# DualGreenHat_schematic.net
KiCad netlist of a schematic drawn in EasyEDA
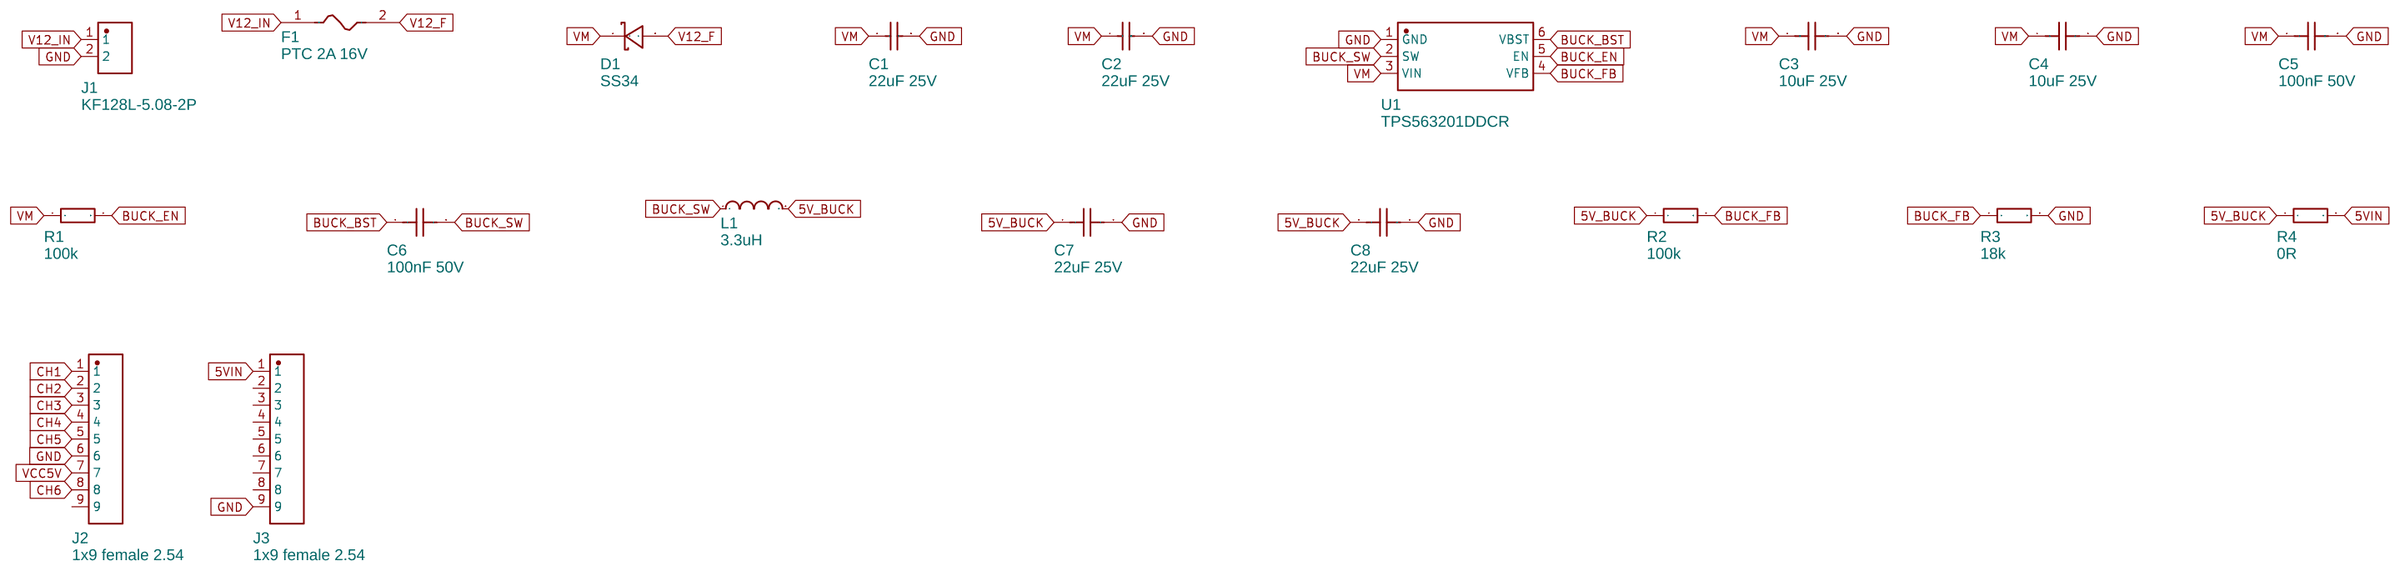
[diagram p0: Power and S3Bat]
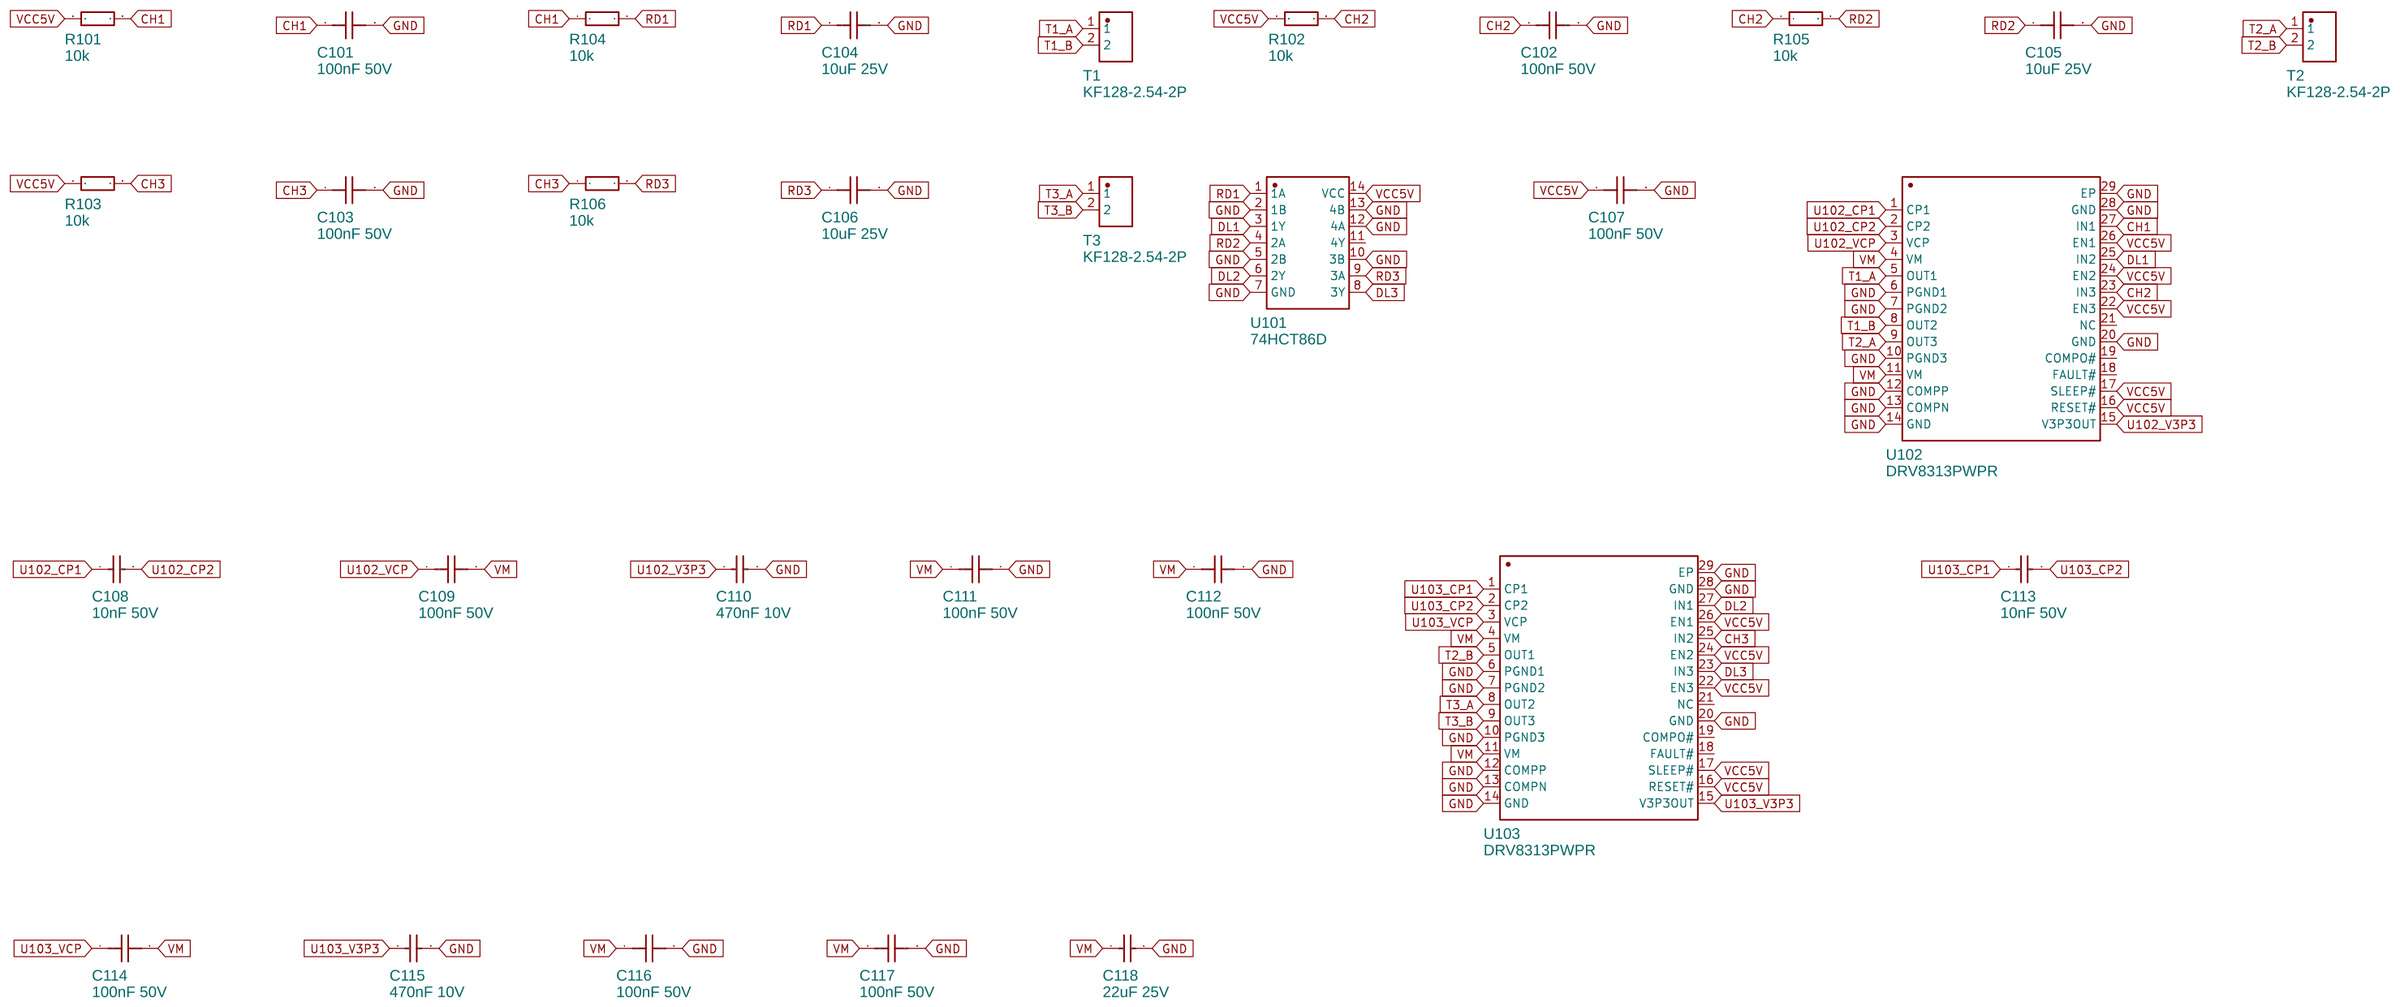
[diagram p1: Channels 1-3]
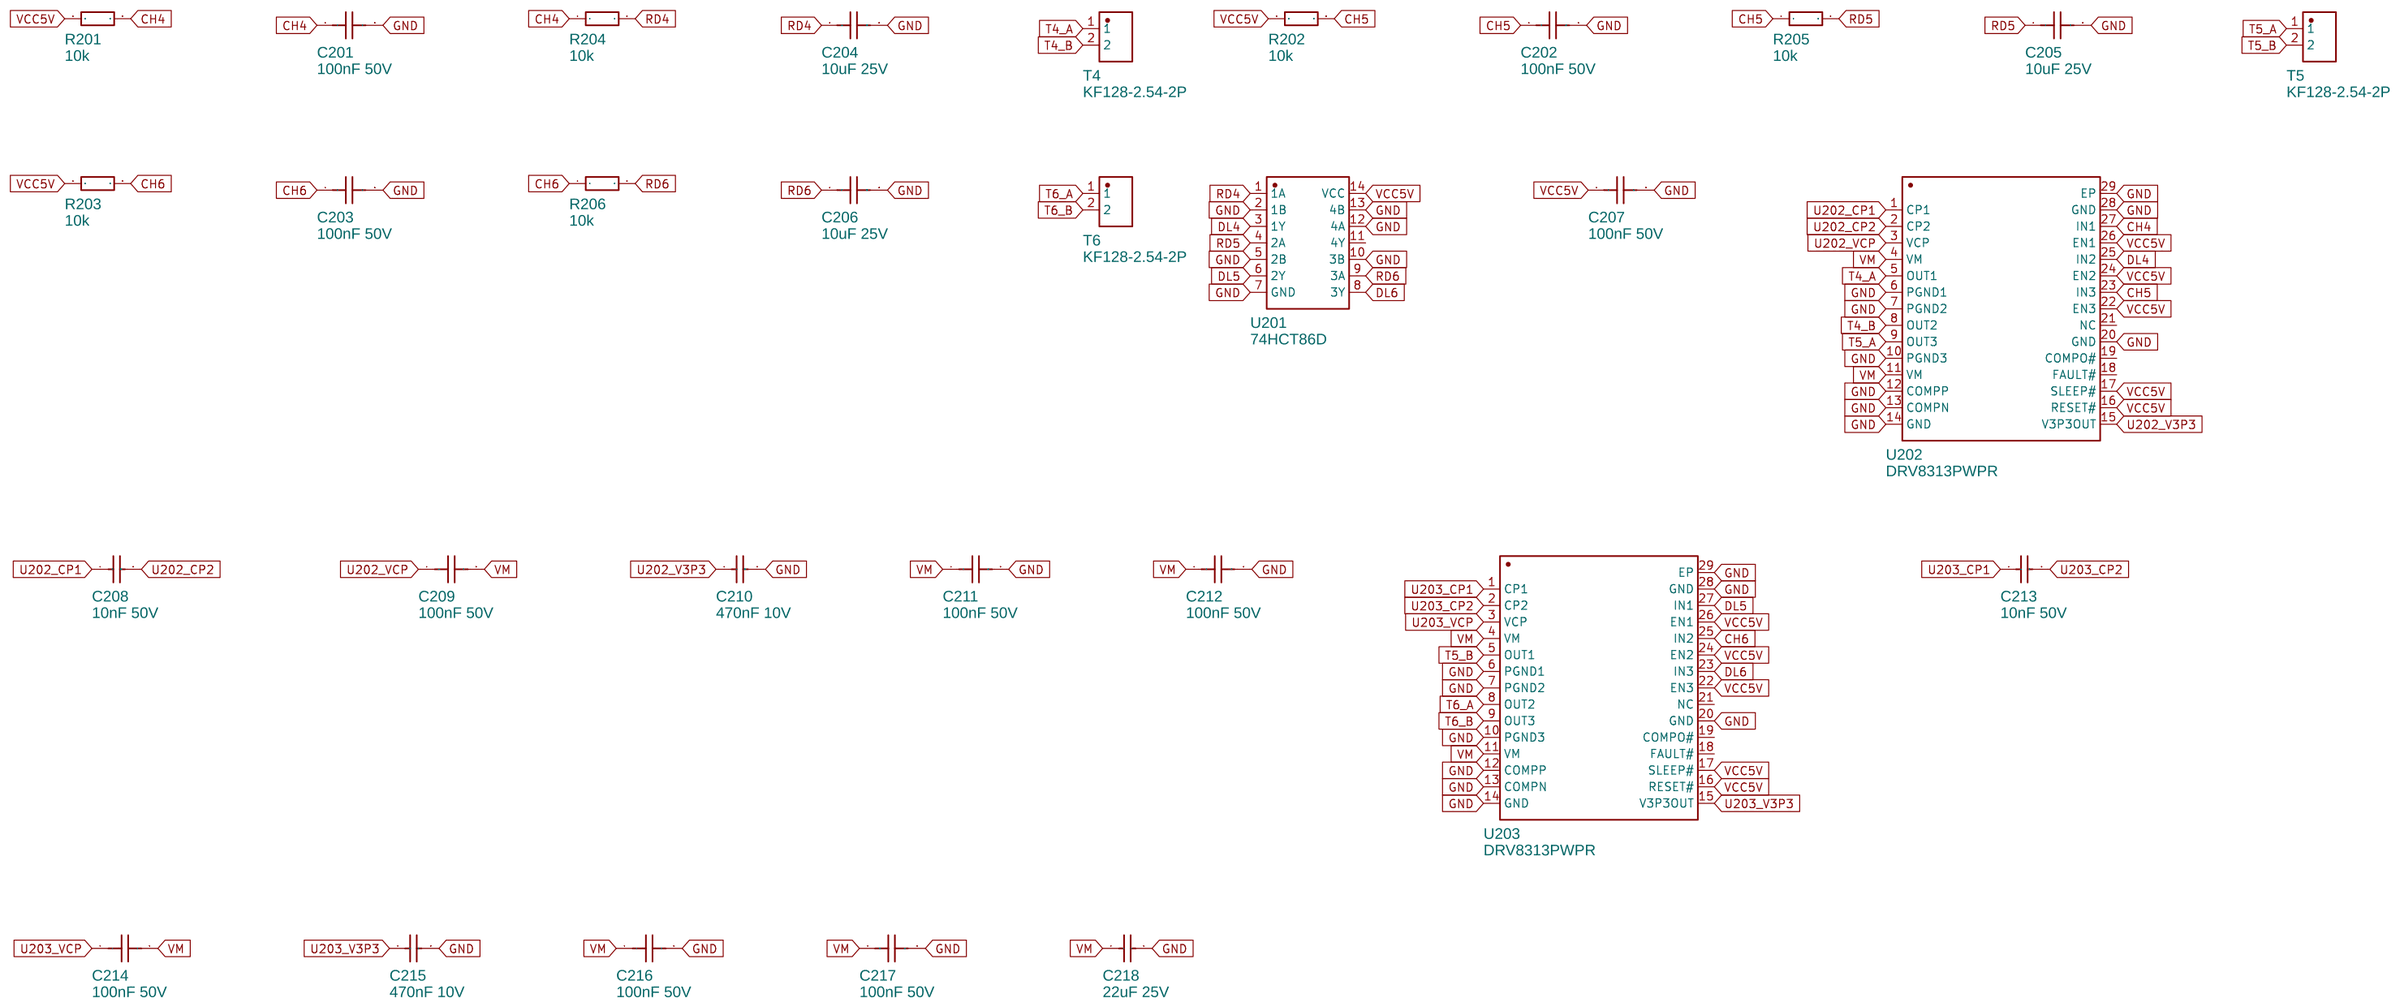
[diagram p2: Channels 4-6]

(export (version "E")
  (design (tool "Eeschema 10.0.6"))
  (components
    (comp (ref "C1")
      (value "22uF 25V")
      (fields
        (field (name "BOM_Manufacturer Part") "CL31A226KAHNNNE")
        (field (name "BOM_Supplier Part") "C12891")
      )
      (libsource (lib "") (part "CL31A226KAHNNNE_1"))
    )
    (comp (ref "C2")
      (value "22uF 25V")
      (fields
        (field (name "BOM_Manufacturer Part") "CL31A226KAHNNNE")
        (field (name "BOM_Supplier Part") "C12891")
      )
      (libsource (lib "") (part "CL31A226KAHNNNE"))
    )
    (comp (ref "C3")
      (value "10uF 25V")
      (fields
        (field (name "BOM_Manufacturer Part") "CL21A106KAYNNNE")
        (field (name "BOM_Supplier Part") "C15850")
      )
      (libsource (lib "") (part "CL21A106KAYNNNE_1"))
    )
    (comp (ref "C4")
      (value "10uF 25V")
      (fields
        (field (name "BOM_Manufacturer Part") "CL21A106KAYNNNE")
        (field (name "BOM_Supplier Part") "C15850")
      )
      (libsource (lib "") (part "CL21A106KAYNNNE"))
    )
    (comp (ref "C5")
      (value "100nF 50V")
      (fields
        (field (name "BOM_Manufacturer Part") "CL05B104KB54PNC")
        (field (name "BOM_Supplier Part") "C307331")
      )
      (libsource (lib "") (part "CL05B104KB54PNC"))
    )
    (comp (ref "C6")
      (value "100nF 50V")
      (fields
        (field (name "BOM_Manufacturer Part") "CL05B104KB54PNC")
        (field (name "BOM_Supplier Part") "C307331")
      )
      (libsource (lib "") (part "CL05B104KB54PNC"))
    )
    (comp (ref "C7")
      (value "22uF 25V")
      (fields
        (field (name "BOM_Manufacturer Part") "CL21A226MAQNNNE")
        (field (name "BOM_Supplier Part") "C45783")
      )
      (libsource (lib "") (part "CL21A226MAQNNNE"))
    )
    (comp (ref "C8")
      (value "22uF 25V")
      (fields
        (field (name "BOM_Manufacturer Part") "CL21A226MAQNNNE")
        (field (name "BOM_Supplier Part") "C45783")
      )
      (libsource (lib "") (part "CL21A226MAQNNNE"))
    )
    (comp (ref "D1")
      (value "SS34")
      (fields (field (name "BOM_Supplier Part") "C8678"))
      (libsource (lib "") (part "SS34"))
    )
    (comp (ref "F1")
      (value "PTC 2A 16V")
      (fields
        (field (name "BOM_Manufacturer Part") "SMD1812P200TF16")
        (field (name "BOM_Supplier Part") "C20812")
      )
      (libsource (lib "") (part "SMD1812P200TF16"))
    )
    (comp (ref "J1")
      (value "KF128L-5.08-2P")
      (fields (field (name "BOM_Supplier Part") "C474940"))
      (libsource (lib "") (part "KF128L-5.08-2P"))
    )
    (comp (ref "J2")
      (value "1x9 female 2.54")
      (fields
        (field (name "BOM_Manufacturer Part") "HX PM2.54-1x9P ZC-Y")
        (field (name "BOM_Supplier Part") "C22438159")
      )
      (libsource (lib "") (part "HX PM2.54-1x9P ZC-Y"))
    )
    (comp (ref "J3")
      (value "1x9 female 2.54")
      (fields
        (field (name "BOM_Manufacturer Part") "HX PM2.54-1x9P ZC-Y")
        (field (name "BOM_Supplier Part") "C22438159")
      )
      (libsource (lib "") (part "HX PM2.54-1x9P ZC-Y"))
    )
    (comp (ref "L1")
      (value "3.3uH")
      (fields
        (field (name "BOM_Manufacturer Part") "SWPA4030S3R3MT")
        (field (name "BOM_Supplier Part") "C15269")
      )
      (libsource (lib "") (part "SWPA4030S3R3MT"))
    )
    (comp (ref "R1")
      (value "100k")
      (fields
        (field (name "BOM_Manufacturer Part") "0402WGF1003TCE")
        (field (name "BOM_Supplier Part") "C25741")
      )
      (libsource (lib "") (part "0402WGF1003TCE"))
    )
    (comp (ref "R2")
      (value "100k")
      (fields
        (field (name "BOM_Manufacturer Part") "0402WGF1003TCE")
        (field (name "BOM_Supplier Part") "C25741")
      )
      (libsource (lib "") (part "0402WGF1003TCE"))
    )
    (comp (ref "R3")
      (value "18k")
      (fields
        (field (name "BOM_Manufacturer Part") "0603WAF1802T5E")
        (field (name "BOM_Supplier Part") "C25810")
      )
      (libsource (lib "") (part "0603WAF1802T5E"))
    )
    (comp (ref "R4")
      (value "0R")
      (fields
        (field (name "BOM_Manufacturer Part") "0805W8F0000T5E")
        (field (name "BOM_Supplier Part") "C17477")
      )
      (libsource (lib "") (part "0805W8F0000T5E"))
    )
    (comp (ref "U1")
      (value "TPS563201DDCR")
      (fields (field (name "BOM_Supplier Part") "C116592"))
      (libsource (lib "") (part "TPS563201DDCR"))
    )
    (comp (ref "C101")
      (value "100nF 50V")
      (fields
        (field (name "BOM_Manufacturer Part") "CL05B104KB54PNC")
        (field (name "BOM_Supplier Part") "C307331")
      )
      (libsource (lib "") (part "CL05B104KB54PNC_1"))
    )
    (comp (ref "C102")
      (value "100nF 50V")
      (fields
        (field (name "BOM_Manufacturer Part") "CL05B104KB54PNC")
        (field (name "BOM_Supplier Part") "C307331")
      )
      (libsource (lib "") (part "CL05B104KB54PNC_1"))
    )
    (comp (ref "C103")
      (value "100nF 50V")
      (fields
        (field (name "BOM_Manufacturer Part") "CL05B104KB54PNC")
        (field (name "BOM_Supplier Part") "C307331")
      )
      (libsource (lib "") (part "CL05B104KB54PNC_1"))
    )
    (comp (ref "C104")
      (value "10uF 25V")
      (fields
        (field (name "BOM_Manufacturer Part") "CL21A106KAYNNNE")
        (field (name "BOM_Supplier Part") "C15850")
      )
      (libsource (lib "") (part "CL21A106KAYNNNE"))
    )
    (comp (ref "C105")
      (value "10uF 25V")
      (fields
        (field (name "BOM_Manufacturer Part") "CL21A106KAYNNNE")
        (field (name "BOM_Supplier Part") "C15850")
      )
      (libsource (lib "") (part "CL21A106KAYNNNE"))
    )
    (comp (ref "C106")
      (value "10uF 25V")
      (fields
        (field (name "BOM_Manufacturer Part") "CL21A106KAYNNNE")
        (field (name "BOM_Supplier Part") "C15850")
      )
      (libsource (lib "") (part "CL21A106KAYNNNE"))
    )
    (comp (ref "C107")
      (value "100nF 50V")
      (fields
        (field (name "BOM_Manufacturer Part") "CL05B104KB54PNC")
        (field (name "BOM_Supplier Part") "C307331")
      )
      (libsource (lib "") (part "CL05B104KB54PNC_1"))
    )
    (comp (ref "C108")
      (value "10nF 50V")
      (fields
        (field (name "BOM_Manufacturer Part") "CL05B103KB5NNNC")
        (field (name "BOM_Supplier Part") "C15195")
      )
      (libsource (lib "") (part "CL05B103KB5NNNC"))
    )
    (comp (ref "C109")
      (value "100nF 50V")
      (fields
        (field (name "BOM_Manufacturer Part") "CL05B104KB54PNC")
        (field (name "BOM_Supplier Part") "C307331")
      )
      (libsource (lib "") (part "CL05B104KB54PNC"))
    )
    (comp (ref "C110")
      (value "470nF 10V")
      (fields
        (field (name "BOM_Manufacturer Part") "CL05A474KP5NNNC")
        (field (name "BOM_Supplier Part") "C47339")
      )
      (libsource (lib "") (part "CL05A474KP5NNNC"))
    )
    (comp (ref "C111")
      (value "100nF 50V")
      (fields
        (field (name "BOM_Manufacturer Part") "CL05B104KB54PNC")
        (field (name "BOM_Supplier Part") "C307331")
      )
      (libsource (lib "") (part "CL05B104KB54PNC"))
    )
    (comp (ref "C112")
      (value "100nF 50V")
      (fields
        (field (name "BOM_Manufacturer Part") "CL05B104KB54PNC")
        (field (name "BOM_Supplier Part") "C307331")
      )
      (libsource (lib "") (part "CL05B104KB54PNC_1"))
    )
    (comp (ref "C113")
      (value "10nF 50V")
      (fields
        (field (name "BOM_Manufacturer Part") "CL05B103KB5NNNC")
        (field (name "BOM_Supplier Part") "C15195")
      )
      (libsource (lib "") (part "CL05B103KB5NNNC_1"))
    )
    (comp (ref "C114")
      (value "100nF 50V")
      (fields
        (field (name "BOM_Manufacturer Part") "CL05B104KB54PNC")
        (field (name "BOM_Supplier Part") "C307331")
      )
      (libsource (lib "") (part "CL05B104KB54PNC"))
    )
    (comp (ref "C115")
      (value "470nF 10V")
      (fields
        (field (name "BOM_Manufacturer Part") "CL05A474KP5NNNC")
        (field (name "BOM_Supplier Part") "C47339")
      )
      (libsource (lib "") (part "CL05A474KP5NNNC"))
    )
    (comp (ref "C116")
      (value "100nF 50V")
      (fields
        (field (name "BOM_Manufacturer Part") "CL05B104KB54PNC")
        (field (name "BOM_Supplier Part") "C307331")
      )
      (libsource (lib "") (part "CL05B104KB54PNC"))
    )
    (comp (ref "C117")
      (value "100nF 50V")
      (fields
        (field (name "BOM_Manufacturer Part") "CL05B104KB54PNC")
        (field (name "BOM_Supplier Part") "C307331")
      )
      (libsource (lib "") (part "CL05B104KB54PNC_1"))
    )
    (comp (ref "C118")
      (value "22uF 25V")
      (fields
        (field (name "BOM_Manufacturer Part") "CL31A226KAHNNNE")
        (field (name "BOM_Supplier Part") "C12891")
      )
      (libsource (lib "") (part "CL31A226KAHNNNE"))
    )
    (comp (ref "R101")
      (value "10k")
      (fields
        (field (name "BOM_Manufacturer Part") "0402WGF1002TCE")
        (field (name "BOM_Supplier Part") "C25744")
      )
      (libsource (lib "") (part "0402WGF1002TCE"))
    )
    (comp (ref "R102")
      (value "10k")
      (fields
        (field (name "BOM_Manufacturer Part") "0402WGF1002TCE")
        (field (name "BOM_Supplier Part") "C25744")
      )
      (libsource (lib "") (part "0402WGF1002TCE"))
    )
    (comp (ref "R103")
      (value "10k")
      (fields
        (field (name "BOM_Manufacturer Part") "0402WGF1002TCE")
        (field (name "BOM_Supplier Part") "C25744")
      )
      (libsource (lib "") (part "0402WGF1002TCE"))
    )
    (comp (ref "R104")
      (value "10k")
      (fields
        (field (name "BOM_Manufacturer Part") "0402WGF1002TCE")
        (field (name "BOM_Supplier Part") "C25744")
      )
      (libsource (lib "") (part "0402WGF1002TCE"))
    )
    (comp (ref "R105")
      (value "10k")
      (fields
        (field (name "BOM_Manufacturer Part") "0402WGF1002TCE")
        (field (name "BOM_Supplier Part") "C25744")
      )
      (libsource (lib "") (part "0402WGF1002TCE"))
    )
    (comp (ref "R106")
      (value "10k")
      (fields
        (field (name "BOM_Manufacturer Part") "0402WGF1002TCE")
        (field (name "BOM_Supplier Part") "C25744")
      )
      (libsource (lib "") (part "0402WGF1002TCE"))
    )
    (comp (ref "T1")
      (value "KF128-2.54-2P")
      (fields (field (name "BOM_Supplier Part") "C474920"))
      (libsource (lib "") (part "KF128-2.54-2P"))
    )
    (comp (ref "T2")
      (value "KF128-2.54-2P")
      (fields (field (name "BOM_Supplier Part") "C474920"))
      (libsource (lib "") (part "KF128-2.54-2P"))
    )
    (comp (ref "T3")
      (value "KF128-2.54-2P")
      (fields (field (name "BOM_Supplier Part") "C474920"))
      (libsource (lib "") (part "KF128-2.54-2P"))
    )
    (comp (ref "U101")
      (value "74HCT86D")
      (fields
        (field (name "BOM_Manufacturer Part") "74HCT86D,653")
        (field (name "BOM_Supplier Part") "C6005")
      )
      (libsource (lib "") (part "74HCT86D,653"))
    )
    (comp (ref "U102")
      (value "DRV8313PWPR")
      (fields (field (name "BOM_Supplier Part") "C92482"))
      (libsource (lib "") (part "DRV8313PWPR"))
    )
    (comp (ref "U103")
      (value "DRV8313PWPR")
      (fields (field (name "BOM_Supplier Part") "C92482"))
      (libsource (lib "") (part "DRV8313PWPR"))
    )
    (comp (ref "C201")
      (value "100nF 50V")
      (fields
        (field (name "BOM_Manufacturer Part") "CL05B104KB54PNC")
        (field (name "BOM_Supplier Part") "C307331")
      )
      (libsource (lib "") (part "CL05B104KB54PNC"))
    )
    (comp (ref "C202")
      (value "100nF 50V")
      (fields
        (field (name "BOM_Manufacturer Part") "CL05B104KB54PNC")
        (field (name "BOM_Supplier Part") "C307331")
      )
      (libsource (lib "") (part "CL05B104KB54PNC"))
    )
    (comp (ref "C203")
      (value "100nF 50V")
      (fields
        (field (name "BOM_Manufacturer Part") "CL05B104KB54PNC")
        (field (name "BOM_Supplier Part") "C307331")
      )
      (libsource (lib "") (part "CL05B104KB54PNC"))
    )
    (comp (ref "C204")
      (value "10uF 25V")
      (fields
        (field (name "BOM_Manufacturer Part") "CL21A106KAYNNNE")
        (field (name "BOM_Supplier Part") "C15850")
      )
      (libsource (lib "") (part "CL21A106KAYNNNE"))
    )
    (comp (ref "C205")
      (value "10uF 25V")
      (fields
        (field (name "BOM_Manufacturer Part") "CL21A106KAYNNNE")
        (field (name "BOM_Supplier Part") "C15850")
      )
      (libsource (lib "") (part "CL21A106KAYNNNE"))
    )
    (comp (ref "C206")
      (value "10uF 25V")
      (fields
        (field (name "BOM_Manufacturer Part") "CL21A106KAYNNNE")
        (field (name "BOM_Supplier Part") "C15850")
      )
      (libsource (lib "") (part "CL21A106KAYNNNE"))
    )
    (comp (ref "C207")
      (value "100nF 50V")
      (fields
        (field (name "BOM_Manufacturer Part") "CL05B104KB54PNC")
        (field (name "BOM_Supplier Part") "C307331")
      )
      (libsource (lib "") (part "CL05B104KB54PNC"))
    )
    (comp (ref "C208")
      (value "10nF 50V")
      (fields
        (field (name "BOM_Manufacturer Part") "CL05B103KB5NNNC")
        (field (name "BOM_Supplier Part") "C15195")
      )
      (libsource (lib "") (part "CL05B103KB5NNNC_1"))
    )
    (comp (ref "C209")
      (value "100nF 50V")
      (fields
        (field (name "BOM_Manufacturer Part") "CL05B104KB54PNC")
        (field (name "BOM_Supplier Part") "C307331")
      )
      (libsource (lib "") (part "CL05B104KB54PNC_1"))
    )
    (comp (ref "C210")
      (value "470nF 10V")
      (fields
        (field (name "BOM_Manufacturer Part") "CL05A474KP5NNNC")
        (field (name "BOM_Supplier Part") "C47339")
      )
      (libsource (lib "") (part "CL05A474KP5NNNC"))
    )
    (comp (ref "C211")
      (value "100nF 50V")
      (fields
        (field (name "BOM_Manufacturer Part") "CL05B104KB54PNC")
        (field (name "BOM_Supplier Part") "C307331")
      )
      (libsource (lib "") (part "CL05B104KB54PNC_1"))
    )
    (comp (ref "C212")
      (value "100nF 50V")
      (fields
        (field (name "BOM_Manufacturer Part") "CL05B104KB54PNC")
        (field (name "BOM_Supplier Part") "C307331")
      )
      (libsource (lib "") (part "CL05B104KB54PNC"))
    )
    (comp (ref "C213")
      (value "10nF 50V")
      (fields
        (field (name "BOM_Manufacturer Part") "CL05B103KB5NNNC")
        (field (name "BOM_Supplier Part") "C15195")
      )
      (libsource (lib "") (part "CL05B103KB5NNNC"))
    )
    (comp (ref "C214")
      (value "100nF 50V")
      (fields
        (field (name "BOM_Manufacturer Part") "CL05B104KB54PNC")
        (field (name "BOM_Supplier Part") "C307331")
      )
      (libsource (lib "") (part "CL05B104KB54PNC_1"))
    )
    (comp (ref "C215")
      (value "470nF 10V")
      (fields
        (field (name "BOM_Manufacturer Part") "CL05A474KP5NNNC")
        (field (name "BOM_Supplier Part") "C47339")
      )
      (libsource (lib "") (part "CL05A474KP5NNNC"))
    )
    (comp (ref "C216")
      (value "100nF 50V")
      (fields
        (field (name "BOM_Manufacturer Part") "CL05B104KB54PNC")
        (field (name "BOM_Supplier Part") "C307331")
      )
      (libsource (lib "") (part "CL05B104KB54PNC_1"))
    )
    (comp (ref "C217")
      (value "100nF 50V")
      (fields
        (field (name "BOM_Manufacturer Part") "CL05B104KB54PNC")
        (field (name "BOM_Supplier Part") "C307331")
      )
      (libsource (lib "") (part "CL05B104KB54PNC"))
    )
    (comp (ref "C218")
      (value "22uF 25V")
      (fields
        (field (name "BOM_Manufacturer Part") "CL31A226KAHNNNE")
        (field (name "BOM_Supplier Part") "C12891")
      )
      (libsource (lib "") (part "CL31A226KAHNNNE"))
    )
    (comp (ref "R201")
      (value "10k")
      (fields
        (field (name "BOM_Manufacturer Part") "0402WGF1002TCE")
        (field (name "BOM_Supplier Part") "C25744")
      )
      (libsource (lib "") (part "0402WGF1002TCE"))
    )
    (comp (ref "R202")
      (value "10k")
      (fields
        (field (name "BOM_Manufacturer Part") "0402WGF1002TCE")
        (field (name "BOM_Supplier Part") "C25744")
      )
      (libsource (lib "") (part "0402WGF1002TCE"))
    )
    (comp (ref "R203")
      (value "10k")
      (fields
        (field (name "BOM_Manufacturer Part") "0402WGF1002TCE")
        (field (name "BOM_Supplier Part") "C25744")
      )
      (libsource (lib "") (part "0402WGF1002TCE"))
    )
    (comp (ref "R204")
      (value "10k")
      (fields
        (field (name "BOM_Manufacturer Part") "0402WGF1002TCE")
        (field (name "BOM_Supplier Part") "C25744")
      )
      (libsource (lib "") (part "0402WGF1002TCE"))
    )
    (comp (ref "R205")
      (value "10k")
      (fields
        (field (name "BOM_Manufacturer Part") "0402WGF1002TCE")
        (field (name "BOM_Supplier Part") "C25744")
      )
      (libsource (lib "") (part "0402WGF1002TCE"))
    )
    (comp (ref "R206")
      (value "10k")
      (fields
        (field (name "BOM_Manufacturer Part") "0402WGF1002TCE")
        (field (name "BOM_Supplier Part") "C25744")
      )
      (libsource (lib "") (part "0402WGF1002TCE"))
    )
    (comp (ref "T4")
      (value "KF128-2.54-2P")
      (fields (field (name "BOM_Supplier Part") "C474920"))
      (libsource (lib "") (part "KF128-2.54-2P"))
    )
    (comp (ref "T5")
      (value "KF128-2.54-2P")
      (fields (field (name "BOM_Supplier Part") "C474920"))
      (libsource (lib "") (part "KF128-2.54-2P"))
    )
    (comp (ref "T6")
      (value "KF128-2.54-2P")
      (fields (field (name "BOM_Supplier Part") "C474920"))
      (libsource (lib "") (part "KF128-2.54-2P"))
    )
    (comp (ref "U201")
      (value "74HCT86D")
      (fields
        (field (name "BOM_Manufacturer Part") "74HCT86D,653")
        (field (name "BOM_Supplier Part") "C6005")
      )
      (libsource (lib "") (part "74HCT86D,653"))
    )
    (comp (ref "U202")
      (value "DRV8313PWPR")
      (fields (field (name "BOM_Supplier Part") "C92482"))
      (libsource (lib "") (part "DRV8313PWPR"))
    )
    (comp (ref "U203")
      (value "DRV8313PWPR")
      (fields (field (name "BOM_Supplier Part") "C92482"))
      (libsource (lib "") (part "DRV8313PWPR"))
    )
  )
  (nets
    (net (code "1") (name "5VIN") (class "Default")
      (node (ref "J3") (pin "1") (pinfunction "1_1") (pintype "unspecified"))
      (node (ref "R4") (pin "2") (pinfunction "2_2") (pintype "input"))
    )
    (net (code "2") (name "5V_BUCK") (class "Default")
      (node (ref "C7") (pin "1") (pinfunction "1_1") (pintype "unspecified"))
      (node (ref "C8") (pin "1") (pinfunction "1_1") (pintype "unspecified"))
      (node (ref "L1") (pin "2") (pinfunction "2_2") (pintype "unspecified"))
      (node (ref "R2") (pin "1") (pinfunction "1_1") (pintype "input"))
      (node (ref "R4") (pin "1") (pinfunction "1_1") (pintype "input"))
    )
    (net (code "3") (name "BUCK_BST") (class "Default")
      (node (ref "C6") (pin "1") (pinfunction "1_1") (pintype "unspecified"))
      (node (ref "U1") (pin "6") (pinfunction "VBST_6") (pintype "unspecified"))
    )
    (net (code "4") (name "BUCK_EN") (class "Default")
      (node (ref "R1") (pin "2") (pinfunction "2_2") (pintype "input"))
      (node (ref "U1") (pin "5") (pinfunction "EN_5") (pintype "unspecified"))
    )
    (net (code "5") (name "BUCK_FB") (class "Default")
      (node (ref "R2") (pin "2") (pinfunction "2_2") (pintype "input"))
      (node (ref "R3") (pin "1") (pinfunction "1_1") (pintype "input"))
      (node (ref "U1") (pin "4") (pinfunction "VFB_4") (pintype "unspecified"))
    )
    (net (code "6") (name "BUCK_SW") (class "Default")
      (node (ref "C6") (pin "2") (pinfunction "2_2") (pintype "unspecified"))
      (node (ref "L1") (pin "1") (pinfunction "1_1") (pintype "unspecified"))
      (node (ref "U1") (pin "2") (pinfunction "SW_2") (pintype "unspecified"))
    )
    (net (code "7") (name "CH1") (class "Default")
      (node (ref "C101") (pin "1") (pinfunction "1_1") (pintype "unspecified"))
      (node (ref "J2") (pin "1") (pinfunction "1_1") (pintype "unspecified"))
      (node (ref "R101") (pin "2") (pinfunction "2_2") (pintype "input"))
      (node (ref "R104") (pin "1") (pinfunction "1_1") (pintype "input"))
      (node (ref "U102") (pin "27") (pinfunction "IN1_27") (pintype "unspecified"))
    )
    (net (code "8") (name "CH2") (class "Default")
      (node (ref "C102") (pin "1") (pinfunction "1_1") (pintype "unspecified"))
      (node (ref "J2") (pin "2") (pinfunction "2_2") (pintype "unspecified"))
      (node (ref "R102") (pin "2") (pinfunction "2_2") (pintype "input"))
      (node (ref "R105") (pin "1") (pinfunction "1_1") (pintype "input"))
      (node (ref "U102") (pin "23") (pinfunction "IN3_23") (pintype "unspecified"))
    )
    (net (code "9") (name "CH3") (class "Default")
      (node (ref "C103") (pin "1") (pinfunction "1_1") (pintype "unspecified"))
      (node (ref "J2") (pin "3") (pinfunction "3_3") (pintype "unspecified"))
      (node (ref "R103") (pin "2") (pinfunction "2_2") (pintype "input"))
      (node (ref "R106") (pin "1") (pinfunction "1_1") (pintype "input"))
      (node (ref "U103") (pin "25") (pinfunction "IN2_25") (pintype "unspecified"))
    )
    (net (code "10") (name "CH4") (class "Default")
      (node (ref "C201") (pin "1") (pinfunction "1_1") (pintype "unspecified"))
      (node (ref "J2") (pin "4") (pinfunction "4_4") (pintype "unspecified"))
      (node (ref "R201") (pin "2") (pinfunction "2_2") (pintype "input"))
      (node (ref "R204") (pin "1") (pinfunction "1_1") (pintype "input"))
      (node (ref "U202") (pin "27") (pinfunction "IN1_27") (pintype "unspecified"))
    )
    (net (code "11") (name "CH5") (class "Default")
      (node (ref "C202") (pin "1") (pinfunction "1_1") (pintype "unspecified"))
      (node (ref "J2") (pin "5") (pinfunction "5_5") (pintype "unspecified"))
      (node (ref "R202") (pin "2") (pinfunction "2_2") (pintype "input"))
      (node (ref "R205") (pin "1") (pinfunction "1_1") (pintype "input"))
      (node (ref "U202") (pin "23") (pinfunction "IN3_23") (pintype "unspecified"))
    )
    (net (code "12") (name "CH6") (class "Default")
      (node (ref "C203") (pin "1") (pinfunction "1_1") (pintype "unspecified"))
      (node (ref "J2") (pin "8") (pinfunction "8_8") (pintype "unspecified"))
      (node (ref "R203") (pin "2") (pinfunction "2_2") (pintype "input"))
      (node (ref "R206") (pin "1") (pinfunction "1_1") (pintype "input"))
      (node (ref "U203") (pin "25") (pinfunction "IN2_25") (pintype "unspecified"))
    )
    (net (code "13") (name "DL1") (class "Default")
      (node (ref "U101") (pin "3") (pinfunction "1Y_3") (pintype "unspecified"))
      (node (ref "U102") (pin "25") (pinfunction "IN2_25") (pintype "unspecified"))
    )
    (net (code "14") (name "DL2") (class "Default")
      (node (ref "U101") (pin "6") (pinfunction "2Y_6") (pintype "unspecified"))
      (node (ref "U103") (pin "27") (pinfunction "IN1_27") (pintype "unspecified"))
    )
    (net (code "15") (name "DL3") (class "Default")
      (node (ref "U101") (pin "8") (pinfunction "3Y_8") (pintype "unspecified"))
      (node (ref "U103") (pin "23") (pinfunction "IN3_23") (pintype "unspecified"))
    )
    (net (code "16") (name "DL4") (class "Default")
      (node (ref "U201") (pin "3") (pinfunction "1Y_3") (pintype "unspecified"))
      (node (ref "U202") (pin "25") (pinfunction "IN2_25") (pintype "unspecified"))
    )
    (net (code "17") (name "DL5") (class "Default")
      (node (ref "U201") (pin "6") (pinfunction "2Y_6") (pintype "unspecified"))
      (node (ref "U203") (pin "27") (pinfunction "IN1_27") (pintype "unspecified"))
    )
    (net (code "18") (name "DL6") (class "Default")
      (node (ref "U201") (pin "8") (pinfunction "3Y_8") (pintype "unspecified"))
      (node (ref "U203") (pin "23") (pinfunction "IN3_23") (pintype "unspecified"))
    )
    (net (code "19") (name "GND") (class "Default")
      (node (ref "C1") (pin "2") (pinfunction "2_2") (pintype "input"))
      (node (ref "C101") (pin "2") (pinfunction "2_2") (pintype "unspecified"))
      (node (ref "C102") (pin "2") (pinfunction "2_2") (pintype "unspecified"))
      (node (ref "C103") (pin "2") (pinfunction "2_2") (pintype "unspecified"))
      (node (ref "C104") (pin "2") (pinfunction "2_2") (pintype "unspecified"))
      (node (ref "C105") (pin "2") (pinfunction "2_2") (pintype "unspecified"))
      (node (ref "C106") (pin "2") (pinfunction "2_2") (pintype "unspecified"))
      (node (ref "C107") (pin "2") (pinfunction "2_2") (pintype "unspecified"))
      (node (ref "C110") (pin "2") (pinfunction "2_2") (pintype "input"))
      (node (ref "C111") (pin "2") (pinfunction "2_2") (pintype "unspecified"))
      (node (ref "C112") (pin "2") (pinfunction "2_2") (pintype "unspecified"))
      (node (ref "C115") (pin "2") (pinfunction "2_2") (pintype "input"))
      (node (ref "C116") (pin "2") (pinfunction "2_2") (pintype "unspecified"))
      (node (ref "C117") (pin "2") (pinfunction "2_2") (pintype "unspecified"))
      (node (ref "C118") (pin "2") (pinfunction "2_2") (pintype "input"))
      (node (ref "C2") (pin "2") (pinfunction "2_2") (pintype "input"))
      (node (ref "C201") (pin "2") (pinfunction "2_2") (pintype "unspecified"))
      (node (ref "C202") (pin "2") (pinfunction "2_2") (pintype "unspecified"))
      (node (ref "C203") (pin "2") (pinfunction "2_2") (pintype "unspecified"))
      (node (ref "C204") (pin "2") (pinfunction "2_2") (pintype "unspecified"))
      (node (ref "C205") (pin "2") (pinfunction "2_2") (pintype "unspecified"))
      (node (ref "C206") (pin "2") (pinfunction "2_2") (pintype "unspecified"))
      (node (ref "C207") (pin "2") (pinfunction "2_2") (pintype "unspecified"))
      (node (ref "C210") (pin "2") (pinfunction "2_2") (pintype "input"))
      (node (ref "C211") (pin "2") (pinfunction "2_2") (pintype "unspecified"))
      (node (ref "C212") (pin "2") (pinfunction "2_2") (pintype "unspecified"))
      (node (ref "C215") (pin "2") (pinfunction "2_2") (pintype "input"))
      (node (ref "C216") (pin "2") (pinfunction "2_2") (pintype "unspecified"))
      (node (ref "C217") (pin "2") (pinfunction "2_2") (pintype "unspecified"))
      (node (ref "C218") (pin "2") (pinfunction "2_2") (pintype "input"))
      (node (ref "C3") (pin "2") (pinfunction "2_2") (pintype "unspecified"))
      (node (ref "C4") (pin "2") (pinfunction "2_2") (pintype "unspecified"))
      (node (ref "C5") (pin "2") (pinfunction "2_2") (pintype "unspecified"))
      (node (ref "C7") (pin "2") (pinfunction "2_2") (pintype "unspecified"))
      (node (ref "C8") (pin "2") (pinfunction "2_2") (pintype "unspecified"))
      (node (ref "J1") (pin "2") (pinfunction "2_2") (pintype "unspecified"))
      (node (ref "J2") (pin "6") (pinfunction "6_6") (pintype "unspecified"))
      (node (ref "J3") (pin "9") (pinfunction "9_9") (pintype "unspecified"))
      (node (ref "R3") (pin "2") (pinfunction "2_2") (pintype "input"))
      (node (ref "U1") (pin "1") (pinfunction "GND_1") (pintype "unspecified"))
      (node (ref "U101") (pin "10") (pinfunction "3B_10") (pintype "unspecified"))
      (node (ref "U101") (pin "12") (pinfunction "4A_12") (pintype "unspecified"))
      (node (ref "U101") (pin "13") (pinfunction "4B_13") (pintype "unspecified"))
      (node (ref "U101") (pin "2") (pinfunction "1B_2") (pintype "unspecified"))
      (node (ref "U101") (pin "5") (pinfunction "2B_5") (pintype "unspecified"))
      (node (ref "U101") (pin "7") (pinfunction "GND_7") (pintype "unspecified"))
      (node (ref "U102") (pin "10") (pinfunction "PGND3_10") (pintype "unspecified"))
      (node (ref "U102") (pin "12") (pinfunction "COMPP_12") (pintype "unspecified"))
      (node (ref "U102") (pin "13") (pinfunction "COMPN_13") (pintype "unspecified"))
      (node (ref "U102") (pin "14") (pinfunction "GND_14") (pintype "unspecified"))
      (node (ref "U102") (pin "20") (pinfunction "GND_20") (pintype "unspecified"))
      (node (ref "U102") (pin "28") (pinfunction "GND_28") (pintype "unspecified"))
      (node (ref "U102") (pin "29") (pinfunction "EP_29") (pintype "unspecified"))
      (node (ref "U102") (pin "6") (pinfunction "PGND1_6") (pintype "unspecified"))
      (node (ref "U102") (pin "7") (pinfunction "PGND2_7") (pintype "unspecified"))
      (node (ref "U103") (pin "10") (pinfunction "PGND3_10") (pintype "unspecified"))
      (node (ref "U103") (pin "12") (pinfunction "COMPP_12") (pintype "unspecified"))
      (node (ref "U103") (pin "13") (pinfunction "COMPN_13") (pintype "unspecified"))
      (node (ref "U103") (pin "14") (pinfunction "GND_14") (pintype "unspecified"))
      (node (ref "U103") (pin "20") (pinfunction "GND_20") (pintype "unspecified"))
      (node (ref "U103") (pin "28") (pinfunction "GND_28") (pintype "unspecified"))
      (node (ref "U103") (pin "29") (pinfunction "EP_29") (pintype "unspecified"))
      (node (ref "U103") (pin "6") (pinfunction "PGND1_6") (pintype "unspecified"))
      (node (ref "U103") (pin "7") (pinfunction "PGND2_7") (pintype "unspecified"))
      (node (ref "U201") (pin "10") (pinfunction "3B_10") (pintype "unspecified"))
      (node (ref "U201") (pin "12") (pinfunction "4A_12") (pintype "unspecified"))
      (node (ref "U201") (pin "13") (pinfunction "4B_13") (pintype "unspecified"))
      (node (ref "U201") (pin "2") (pinfunction "1B_2") (pintype "unspecified"))
      (node (ref "U201") (pin "5") (pinfunction "2B_5") (pintype "unspecified"))
      (node (ref "U201") (pin "7") (pinfunction "GND_7") (pintype "unspecified"))
      (node (ref "U202") (pin "10") (pinfunction "PGND3_10") (pintype "unspecified"))
      (node (ref "U202") (pin "12") (pinfunction "COMPP_12") (pintype "unspecified"))
      (node (ref "U202") (pin "13") (pinfunction "COMPN_13") (pintype "unspecified"))
      (node (ref "U202") (pin "14") (pinfunction "GND_14") (pintype "unspecified"))
      (node (ref "U202") (pin "20") (pinfunction "GND_20") (pintype "unspecified"))
      (node (ref "U202") (pin "28") (pinfunction "GND_28") (pintype "unspecified"))
      (node (ref "U202") (pin "29") (pinfunction "EP_29") (pintype "unspecified"))
      (node (ref "U202") (pin "6") (pinfunction "PGND1_6") (pintype "unspecified"))
      (node (ref "U202") (pin "7") (pinfunction "PGND2_7") (pintype "unspecified"))
      (node (ref "U203") (pin "10") (pinfunction "PGND3_10") (pintype "unspecified"))
      (node (ref "U203") (pin "12") (pinfunction "COMPP_12") (pintype "unspecified"))
      (node (ref "U203") (pin "13") (pinfunction "COMPN_13") (pintype "unspecified"))
      (node (ref "U203") (pin "14") (pinfunction "GND_14") (pintype "unspecified"))
      (node (ref "U203") (pin "20") (pinfunction "GND_20") (pintype "unspecified"))
      (node (ref "U203") (pin "28") (pinfunction "GND_28") (pintype "unspecified"))
      (node (ref "U203") (pin "29") (pinfunction "EP_29") (pintype "unspecified"))
      (node (ref "U203") (pin "6") (pinfunction "PGND1_6") (pintype "unspecified"))
      (node (ref "U203") (pin "7") (pinfunction "PGND2_7") (pintype "unspecified"))
    )
    (net (code "20") (name "RD1") (class "Default")
      (node (ref "C104") (pin "1") (pinfunction "1_1") (pintype "unspecified"))
      (node (ref "R104") (pin "2") (pinfunction "2_2") (pintype "input"))
      (node (ref "U101") (pin "1") (pinfunction "1A_1") (pintype "unspecified"))
    )
    (net (code "21") (name "RD2") (class "Default")
      (node (ref "C105") (pin "1") (pinfunction "1_1") (pintype "unspecified"))
      (node (ref "R105") (pin "2") (pinfunction "2_2") (pintype "input"))
      (node (ref "U101") (pin "4") (pinfunction "2A_4") (pintype "unspecified"))
    )
    (net (code "22") (name "RD3") (class "Default")
      (node (ref "C106") (pin "1") (pinfunction "1_1") (pintype "unspecified"))
      (node (ref "R106") (pin "2") (pinfunction "2_2") (pintype "input"))
      (node (ref "U101") (pin "9") (pinfunction "3A_9") (pintype "unspecified"))
    )
    (net (code "23") (name "RD4") (class "Default")
      (node (ref "C204") (pin "1") (pinfunction "1_1") (pintype "unspecified"))
      (node (ref "R204") (pin "2") (pinfunction "2_2") (pintype "input"))
      (node (ref "U201") (pin "1") (pinfunction "1A_1") (pintype "unspecified"))
    )
    (net (code "24") (name "RD5") (class "Default")
      (node (ref "C205") (pin "1") (pinfunction "1_1") (pintype "unspecified"))
      (node (ref "R205") (pin "2") (pinfunction "2_2") (pintype "input"))
      (node (ref "U201") (pin "4") (pinfunction "2A_4") (pintype "unspecified"))
    )
    (net (code "25") (name "RD6") (class "Default")
      (node (ref "C206") (pin "1") (pinfunction "1_1") (pintype "unspecified"))
      (node (ref "R206") (pin "2") (pinfunction "2_2") (pintype "input"))
      (node (ref "U201") (pin "9") (pinfunction "3A_9") (pintype "unspecified"))
    )
    (net (code "26") (name "T1_A") (class "Default")
      (node (ref "T1") (pin "1") (pinfunction "1_1") (pintype "unspecified"))
      (node (ref "U102") (pin "5") (pinfunction "OUT1_5") (pintype "unspecified"))
    )
    (net (code "27") (name "T1_B") (class "Default")
      (node (ref "T1") (pin "2") (pinfunction "2_2") (pintype "unspecified"))
      (node (ref "U102") (pin "8") (pinfunction "OUT2_8") (pintype "unspecified"))
    )
    (net (code "28") (name "T2_A") (class "Default")
      (node (ref "T2") (pin "1") (pinfunction "1_1") (pintype "unspecified"))
      (node (ref "U102") (pin "9") (pinfunction "OUT3_9") (pintype "unspecified"))
    )
    (net (code "29") (name "T2_B") (class "Default")
      (node (ref "T2") (pin "2") (pinfunction "2_2") (pintype "unspecified"))
      (node (ref "U103") (pin "5") (pinfunction "OUT1_5") (pintype "unspecified"))
    )
    (net (code "30") (name "T3_A") (class "Default")
      (node (ref "T3") (pin "1") (pinfunction "1_1") (pintype "unspecified"))
      (node (ref "U103") (pin "8") (pinfunction "OUT2_8") (pintype "unspecified"))
    )
    (net (code "31") (name "T3_B") (class "Default")
      (node (ref "T3") (pin "2") (pinfunction "2_2") (pintype "unspecified"))
      (node (ref "U103") (pin "9") (pinfunction "OUT3_9") (pintype "unspecified"))
    )
    (net (code "32") (name "T4_A") (class "Default")
      (node (ref "T4") (pin "1") (pinfunction "1_1") (pintype "unspecified"))
      (node (ref "U202") (pin "5") (pinfunction "OUT1_5") (pintype "unspecified"))
    )
    (net (code "33") (name "T4_B") (class "Default")
      (node (ref "T4") (pin "2") (pinfunction "2_2") (pintype "unspecified"))
      (node (ref "U202") (pin "8") (pinfunction "OUT2_8") (pintype "unspecified"))
    )
    (net (code "34") (name "T5_A") (class "Default")
      (node (ref "T5") (pin "1") (pinfunction "1_1") (pintype "unspecified"))
      (node (ref "U202") (pin "9") (pinfunction "OUT3_9") (pintype "unspecified"))
    )
    (net (code "35") (name "T5_B") (class "Default")
      (node (ref "T5") (pin "2") (pinfunction "2_2") (pintype "unspecified"))
      (node (ref "U203") (pin "5") (pinfunction "OUT1_5") (pintype "unspecified"))
    )
    (net (code "36") (name "T6_A") (class "Default")
      (node (ref "T6") (pin "1") (pinfunction "1_1") (pintype "unspecified"))
      (node (ref "U203") (pin "8") (pinfunction "OUT2_8") (pintype "unspecified"))
    )
    (net (code "37") (name "T6_B") (class "Default")
      (node (ref "T6") (pin "2") (pinfunction "2_2") (pintype "unspecified"))
      (node (ref "U203") (pin "9") (pinfunction "OUT3_9") (pintype "unspecified"))
    )
    (net (code "38") (name "U102_CP1") (class "Default")
      (node (ref "C108") (pin "1") (pinfunction "1_1") (pintype "input"))
      (node (ref "U102") (pin "1") (pinfunction "CP1_1") (pintype "unspecified"))
    )
    (net (code "39") (name "U102_CP2") (class "Default")
      (node (ref "C108") (pin "2") (pinfunction "2_2") (pintype "input"))
      (node (ref "U102") (pin "2") (pinfunction "CP2_2") (pintype "unspecified"))
    )
    (net (code "40") (name "U102_V3P3") (class "Default")
      (node (ref "C110") (pin "1") (pinfunction "1_1") (pintype "input"))
      (node (ref "U102") (pin "15") (pinfunction "V3P3OUT_15") (pintype "unspecified"))
    )
    (net (code "41") (name "U102_VCP") (class "Default")
      (node (ref "C109") (pin "1") (pinfunction "1_1") (pintype "unspecified"))
      (node (ref "U102") (pin "3") (pinfunction "VCP_3") (pintype "unspecified"))
    )
    (net (code "42") (name "U103_CP1") (class "Default")
      (node (ref "C113") (pin "1") (pinfunction "1_1") (pintype "input"))
      (node (ref "U103") (pin "1") (pinfunction "CP1_1") (pintype "unspecified"))
    )
    (net (code "43") (name "U103_CP2") (class "Default")
      (node (ref "C113") (pin "2") (pinfunction "2_2") (pintype "input"))
      (node (ref "U103") (pin "2") (pinfunction "CP2_2") (pintype "unspecified"))
    )
    (net (code "44") (name "U103_V3P3") (class "Default")
      (node (ref "C115") (pin "1") (pinfunction "1_1") (pintype "input"))
      (node (ref "U103") (pin "15") (pinfunction "V3P3OUT_15") (pintype "unspecified"))
    )
    (net (code "45") (name "U103_VCP") (class "Default")
      (node (ref "C114") (pin "1") (pinfunction "1_1") (pintype "unspecified"))
      (node (ref "U103") (pin "3") (pinfunction "VCP_3") (pintype "unspecified"))
    )
    (net (code "46") (name "U202_CP1") (class "Default")
      (node (ref "C208") (pin "1") (pinfunction "1_1") (pintype "input"))
      (node (ref "U202") (pin "1") (pinfunction "CP1_1") (pintype "unspecified"))
    )
    (net (code "47") (name "U202_CP2") (class "Default")
      (node (ref "C208") (pin "2") (pinfunction "2_2") (pintype "input"))
      (node (ref "U202") (pin "2") (pinfunction "CP2_2") (pintype "unspecified"))
    )
    (net (code "48") (name "U202_V3P3") (class "Default")
      (node (ref "C210") (pin "1") (pinfunction "1_1") (pintype "input"))
      (node (ref "U202") (pin "15") (pinfunction "V3P3OUT_15") (pintype "unspecified"))
    )
    (net (code "49") (name "U202_VCP") (class "Default")
      (node (ref "C209") (pin "1") (pinfunction "1_1") (pintype "unspecified"))
      (node (ref "U202") (pin "3") (pinfunction "VCP_3") (pintype "unspecified"))
    )
    (net (code "50") (name "U203_CP1") (class "Default")
      (node (ref "C213") (pin "1") (pinfunction "1_1") (pintype "input"))
      (node (ref "U203") (pin "1") (pinfunction "CP1_1") (pintype "unspecified"))
    )
    (net (code "51") (name "U203_CP2") (class "Default")
      (node (ref "C213") (pin "2") (pinfunction "2_2") (pintype "input"))
      (node (ref "U203") (pin "2") (pinfunction "CP2_2") (pintype "unspecified"))
    )
    (net (code "52") (name "U203_V3P3") (class "Default")
      (node (ref "C215") (pin "1") (pinfunction "1_1") (pintype "input"))
      (node (ref "U203") (pin "15") (pinfunction "V3P3OUT_15") (pintype "unspecified"))
    )
    (net (code "53") (name "U203_VCP") (class "Default")
      (node (ref "C214") (pin "1") (pinfunction "1_1") (pintype "unspecified"))
      (node (ref "U203") (pin "3") (pinfunction "VCP_3") (pintype "unspecified"))
    )
    (net (code "54") (name "V12_F") (class "Default")
      (node (ref "D1") (pin "2") (pinfunction "A_2") (pintype "unspecified"))
      (node (ref "F1") (pin "2") (pinfunction "2_2") (pintype "unspecified"))
    )
    (net (code "55") (name "V12_IN") (class "Default")
      (node (ref "F1") (pin "1") (pinfunction "1_1") (pintype "unspecified"))
      (node (ref "J1") (pin "1") (pinfunction "1_1") (pintype "unspecified"))
    )
    (net (code "56") (name "VCC5V") (class "Default")
      (node (ref "C107") (pin "1") (pinfunction "1_1") (pintype "unspecified"))
      (node (ref "C207") (pin "1") (pinfunction "1_1") (pintype "unspecified"))
      (node (ref "J2") (pin "7") (pinfunction "7_7") (pintype "unspecified"))
      (node (ref "R101") (pin "1") (pinfunction "1_1") (pintype "input"))
      (node (ref "R102") (pin "1") (pinfunction "1_1") (pintype "input"))
      (node (ref "R103") (pin "1") (pinfunction "1_1") (pintype "input"))
      (node (ref "R201") (pin "1") (pinfunction "1_1") (pintype "input"))
      (node (ref "R202") (pin "1") (pinfunction "1_1") (pintype "input"))
      (node (ref "R203") (pin "1") (pinfunction "1_1") (pintype "input"))
      (node (ref "U101") (pin "14") (pinfunction "VCC_14") (pintype "unspecified"))
      (node (ref "U102") (pin "16") (pinfunction "RESET#_16") (pintype "unspecified"))
      (node (ref "U102") (pin "17") (pinfunction "SLEEP#_17") (pintype "unspecified"))
      (node (ref "U102") (pin "22") (pinfunction "EN3_22") (pintype "unspecified"))
      (node (ref "U102") (pin "24") (pinfunction "EN2_24") (pintype "unspecified"))
      (node (ref "U102") (pin "26") (pinfunction "EN1_26") (pintype "unspecified"))
      (node (ref "U103") (pin "16") (pinfunction "RESET#_16") (pintype "unspecified"))
      (node (ref "U103") (pin "17") (pinfunction "SLEEP#_17") (pintype "unspecified"))
      (node (ref "U103") (pin "22") (pinfunction "EN3_22") (pintype "unspecified"))
      (node (ref "U103") (pin "24") (pinfunction "EN2_24") (pintype "unspecified"))
      (node (ref "U103") (pin "26") (pinfunction "EN1_26") (pintype "unspecified"))
      (node (ref "U201") (pin "14") (pinfunction "VCC_14") (pintype "unspecified"))
      (node (ref "U202") (pin "16") (pinfunction "RESET#_16") (pintype "unspecified"))
      (node (ref "U202") (pin "17") (pinfunction "SLEEP#_17") (pintype "unspecified"))
      (node (ref "U202") (pin "22") (pinfunction "EN3_22") (pintype "unspecified"))
      (node (ref "U202") (pin "24") (pinfunction "EN2_24") (pintype "unspecified"))
      (node (ref "U202") (pin "26") (pinfunction "EN1_26") (pintype "unspecified"))
      (node (ref "U203") (pin "16") (pinfunction "RESET#_16") (pintype "unspecified"))
      (node (ref "U203") (pin "17") (pinfunction "SLEEP#_17") (pintype "unspecified"))
      (node (ref "U203") (pin "22") (pinfunction "EN3_22") (pintype "unspecified"))
      (node (ref "U203") (pin "24") (pinfunction "EN2_24") (pintype "unspecified"))
      (node (ref "U203") (pin "26") (pinfunction "EN1_26") (pintype "unspecified"))
    )
    (net (code "57") (name "VM") (class "Default")
      (node (ref "C1") (pin "1") (pinfunction "1_1") (pintype "input"))
      (node (ref "C109") (pin "2") (pinfunction "2_2") (pintype "unspecified"))
      (node (ref "C111") (pin "1") (pinfunction "1_1") (pintype "unspecified"))
      (node (ref "C112") (pin "1") (pinfunction "1_1") (pintype "unspecified"))
      (node (ref "C114") (pin "2") (pinfunction "2_2") (pintype "unspecified"))
      (node (ref "C116") (pin "1") (pinfunction "1_1") (pintype "unspecified"))
      (node (ref "C117") (pin "1") (pinfunction "1_1") (pintype "unspecified"))
      (node (ref "C118") (pin "1") (pinfunction "1_1") (pintype "input"))
      (node (ref "C2") (pin "1") (pinfunction "1_1") (pintype "input"))
      (node (ref "C209") (pin "2") (pinfunction "2_2") (pintype "unspecified"))
      (node (ref "C211") (pin "1") (pinfunction "1_1") (pintype "unspecified"))
      (node (ref "C212") (pin "1") (pinfunction "1_1") (pintype "unspecified"))
      (node (ref "C214") (pin "2") (pinfunction "2_2") (pintype "unspecified"))
      (node (ref "C216") (pin "1") (pinfunction "1_1") (pintype "unspecified"))
      (node (ref "C217") (pin "1") (pinfunction "1_1") (pintype "unspecified"))
      (node (ref "C218") (pin "1") (pinfunction "1_1") (pintype "input"))
      (node (ref "C3") (pin "1") (pinfunction "1_1") (pintype "unspecified"))
      (node (ref "C4") (pin "1") (pinfunction "1_1") (pintype "unspecified"))
      (node (ref "C5") (pin "1") (pinfunction "1_1") (pintype "unspecified"))
      (node (ref "D1") (pin "1") (pinfunction "K_1") (pintype "unspecified"))
      (node (ref "R1") (pin "1") (pinfunction "1_1") (pintype "input"))
      (node (ref "U1") (pin "3") (pinfunction "VIN_3") (pintype "unspecified"))
      (node (ref "U102") (pin "11") (pinfunction "VM_11") (pintype "unspecified"))
      (node (ref "U102") (pin "4") (pinfunction "VM_4") (pintype "unspecified"))
      (node (ref "U103") (pin "11") (pinfunction "VM_11") (pintype "unspecified"))
      (node (ref "U103") (pin "4") (pinfunction "VM_4") (pintype "unspecified"))
      (node (ref "U202") (pin "11") (pinfunction "VM_11") (pintype "unspecified"))
      (node (ref "U202") (pin "4") (pinfunction "VM_4") (pintype "unspecified"))
      (node (ref "U203") (pin "11") (pinfunction "VM_11") (pintype "unspecified"))
      (node (ref "U203") (pin "4") (pinfunction "VM_4") (pintype "unspecified"))
    )
    (net (code "58") (name "unconnected-(J2-Pad9)") (class "Default")
      (node (ref "J2") (pin "9") (pinfunction "9_9") (pintype "unspecified"))
    )
    (net (code "59") (name "unconnected-(J3-Pad2)") (class "Default")
      (node (ref "J3") (pin "2") (pinfunction "2_2") (pintype "unspecified"))
    )
    (net (code "60") (name "unconnected-(J3-Pad3)") (class "Default")
      (node (ref "J3") (pin "3") (pinfunction "3_3") (pintype "unspecified"))
    )
    (net (code "61") (name "unconnected-(J3-Pad4)") (class "Default")
      (node (ref "J3") (pin "4") (pinfunction "4_4") (pintype "unspecified"))
    )
    (net (code "62") (name "unconnected-(J3-Pad5)") (class "Default")
      (node (ref "J3") (pin "5") (pinfunction "5_5") (pintype "unspecified"))
    )
    (net (code "63") (name "unconnected-(J3-Pad6)") (class "Default")
      (node (ref "J3") (pin "6") (pinfunction "6_6") (pintype "unspecified"))
    )
    (net (code "64") (name "unconnected-(J3-Pad7)") (class "Default")
      (node (ref "J3") (pin "7") (pinfunction "7_7") (pintype "unspecified"))
    )
    (net (code "65") (name "unconnected-(J3-Pad8)") (class "Default")
      (node (ref "J3") (pin "8") (pinfunction "8_8") (pintype "unspecified"))
    )
    (net (code "66") (name "unconnected-(U101-4Y-Pad11)") (class "Default")
      (node (ref "U101") (pin "11") (pinfunction "4Y_11") (pintype "unspecified"))
    )
    (net (code "67") (name "unconnected-(U102-COMPO#-Pad19)") (class "Default")
      (node (ref "U102") (pin "19") (pinfunction "COMPO#_19") (pintype "unspecified"))
    )
    (net (code "68") (name "unconnected-(U102-FAULT#-Pad18)") (class "Default")
      (node (ref "U102") (pin "18") (pinfunction "FAULT#_18") (pintype "unspecified"))
    )
    (net (code "69") (name "unconnected-(U102-NC-Pad21)") (class "Default")
      (node (ref "U102") (pin "21") (pinfunction "NC_21") (pintype "unspecified"))
    )
    (net (code "70") (name "unconnected-(U103-COMPO#-Pad19)") (class "Default")
      (node (ref "U103") (pin "19") (pinfunction "COMPO#_19") (pintype "unspecified"))
    )
    (net (code "71") (name "unconnected-(U103-FAULT#-Pad18)") (class "Default")
      (node (ref "U103") (pin "18") (pinfunction "FAULT#_18") (pintype "unspecified"))
    )
    (net (code "72") (name "unconnected-(U103-NC-Pad21)") (class "Default")
      (node (ref "U103") (pin "21") (pinfunction "NC_21") (pintype "unspecified"))
    )
    (net (code "73") (name "unconnected-(U201-4Y-Pad11)") (class "Default")
      (node (ref "U201") (pin "11") (pinfunction "4Y_11") (pintype "unspecified"))
    )
    (net (code "74") (name "unconnected-(U202-COMPO#-Pad19)") (class "Default")
      (node (ref "U202") (pin "19") (pinfunction "COMPO#_19") (pintype "unspecified"))
    )
    (net (code "75") (name "unconnected-(U202-FAULT#-Pad18)") (class "Default")
      (node (ref "U202") (pin "18") (pinfunction "FAULT#_18") (pintype "unspecified"))
    )
    (net (code "76") (name "unconnected-(U202-NC-Pad21)") (class "Default")
      (node (ref "U202") (pin "21") (pinfunction "NC_21") (pintype "unspecified"))
    )
    (net (code "77") (name "unconnected-(U203-COMPO#-Pad19)") (class "Default")
      (node (ref "U203") (pin "19") (pinfunction "COMPO#_19") (pintype "unspecified"))
    )
    (net (code "78") (name "unconnected-(U203-FAULT#-Pad18)") (class "Default")
      (node (ref "U203") (pin "18") (pinfunction "FAULT#_18") (pintype "unspecified"))
    )
    (net (code "79") (name "unconnected-(U203-NC-Pad21)") (class "Default")
      (node (ref "U203") (pin "21") (pinfunction "NC_21") (pintype "unspecified"))
    )
  )
)
